# Sheet1.net
KiCad netlist of a schematic drawn in Altium Designer
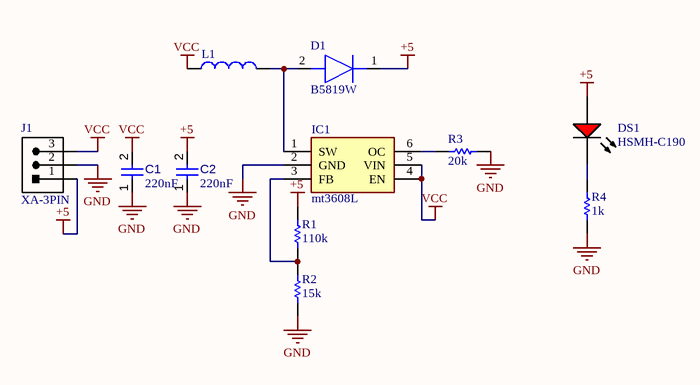
[diagram p0: Sheet1.SchDoc]

(export (version "E")
  (design (tool "Eeschema 10.0.6"))
  (components
    (comp (ref "C1")
      (value "220nF")
      (footprint "CAPC0805(2012)145_L")
      (fields (field (name "Comment") "C0805C224K5RACTU"))
      (libsource (lib "Americas- Northwestern Formula Racing- Northwestern University") (part "CAP-NP-2"))
    )
    (comp (ref "C2")
      (value "220nF")
      (footprint "CAPC0805(2012)145_L")
      (fields (field (name "Comment") "C0805C224K5RACTU"))
      (libsource (lib "Americas- Northwestern Formula Racing- Northwestern University") (part "CAP-NP-2"))
    )
    (comp (ref "D1")
      (value "B5819W")
      (footprint "SamacSys:SOD3716X125N")
      (description "Diode")
      (libsource (lib "*") (part "B5819W"))
    )
    (comp (ref "DS1")
      (value "HSMH-C190")
      (footprint "AVAG-HSMX-C190_V")
      (description "LED Uni-Color Red, 65 mW, 20 mA, -40 to 85 degC, 2-Pin SMD, RoHS, Tape and Reel")
      (fields (field (name "POWER") "78mW") (field (name "MANUFACTURER") "Avago"))
      (libsource (lib "Americas- Northwestern Formula Racing- Northwestern University") (part "LED-RED-AK-2"))
    )
    (comp (ref "IC1")
      (value "mt3608L")
      (footprint "SamacSys:SOT95P280X145-6N")
      (description "Integrated Circuit")
      (libsource (lib "*") (part "mt3608L"))
    )
    (comp (ref "J1")
      (value "XA-3PIN")
      (footprint "XA-3PIN-Footprint-1")
      (description "3 pin JST Connector")
      (libsource (lib "Americas- Northwestern Formula Racing- Northwestern University") (part "XA-3PIN"))
    )
    (comp (ref "L1")
      (value "MBKK2012T4R7M")
      (footprint "INDC2520X120X60LL20T20")
      (description "General Purpose Inductor, 4.7uH, 20%, 1 Element, Metal-Core, SMD, 0805")
      (fields (field (name "TOLERANCE") "20%"))
      (libsource (lib "Americas- Northwestern Formula Racing- Northwestern University") (part "IND-2"))
    )
    (comp (ref "R1")
      (value "110k")
      (footprint "RESC0402(1005)_L")
      (fields
        (field (name "POWER") "50mW")
        (field (name "TOLERANCE") "1%")
        (field (name "Comment") "ERJ-1GNF1103C")
      )
      (libsource (lib "Americas- Northwestern Formula Racing- Northwestern University") (part "RES-2"))
    )
    (comp (ref "R2")
      (value "15k")
      (footprint "RESC0603(1608)_L")
      (description "Fixed Resistor, Thin Film, 0.1W, 15000ohm, 75V, 0.1% +/-Tol, 25ppm/Cel, Surface Mount, 0603")
      (fields (field (name "TOLERANCE") "0.1%") (field (name "POWER") "100mW"))
      (libsource (lib "Americas- Northwestern Formula Racing- Northwestern University") (part "RES-2"))
    )
    (comp (ref "R3")
      (value "20k")
      (footprint "RESC1608X55X30LL15T15")
      (fields
        (field (name "TOLERANCE") "1%")
        (field (name "POWER") "100mW")
        (field (name "Comment") "ERJ-3EKF2002V")
      )
      (libsource (lib "Americas- Northwestern Formula Racing- Northwestern University") (part "RES-2"))
    )
    (comp (ref "R4")
      (value "1k")
      (footprint "RESC0603(1608)_L")
      (fields
        (field (name "TOLERANCE") "1%")
        (field (name "POWER") "100mW")
        (field (name "Comment") "RMCF0603FT1K00")
      )
      (libsource (lib "Americas- Northwestern Formula Racing- Northwestern University") (part "RES-2"))
    )
  )
  (nets
    (net (code "1") (name "+5") (class "Default")
      (node (ref "C2") (pin "2") (pinfunction "2_2") (pintype "passive"))
      (node (ref "D1") (pin "1") (pinfunction "K_1") (pintype "passive"))
      (node (ref "DS1") (pin "1") (pinfunction "A_1") (pintype "passive"))
      (node (ref "J1") (pin "1") (pinfunction "1_1") (pintype "passive"))
      (node (ref "R1") (pin "2") (pinfunction "2_2") (pintype "passive"))
    )
    (net (code "2") (name "GND") (class "Default")
      (node (ref "C1") (pin "1") (pinfunction "1_1") (pintype "passive"))
      (node (ref "C2") (pin "1") (pinfunction "1_1") (pintype "passive"))
      (node (ref "IC1") (pin "2") (pinfunction "GND_2") (pintype "passive"))
      (node (ref "J1") (pin "2") (pinfunction "2_2") (pintype "passive"))
      (node (ref "R2") (pin "2") (pinfunction "2_2") (pintype "passive"))
      (node (ref "R3") (pin "2") (pinfunction "2_2") (pintype "passive"))
      (node (ref "R4") (pin "2") (pinfunction "2_2") (pintype "passive"))
    )
    (net (code "3") (name "Net-(D1-A)") (class "Default")
      (node (ref "D1") (pin "2") (pinfunction "A_2") (pintype "passive"))
      (node (ref "IC1") (pin "1") (pinfunction "SW_1") (pintype "passive"))
      (node (ref "L1") (pin "2") (pinfunction "2_2") (pintype "passive"))
    )
    (net (code "4") (name "Net-(DS1-K)") (class "Default")
      (node (ref "DS1") (pin "2") (pinfunction "K_2") (pintype "passive"))
      (node (ref "R4") (pin "1") (pinfunction "1_1") (pintype "passive"))
    )
    (net (code "5") (name "Net-(IC1-FB)") (class "Default")
      (node (ref "IC1") (pin "3") (pinfunction "FB_3") (pintype "passive"))
      (node (ref "R1") (pin "1") (pinfunction "1_1") (pintype "passive"))
      (node (ref "R2") (pin "1") (pinfunction "1_1") (pintype "passive"))
    )
    (net (code "6") (name "Net-(IC1-OC)") (class "Default")
      (node (ref "IC1") (pin "6") (pinfunction "OC_6") (pintype "passive"))
      (node (ref "R3") (pin "1") (pinfunction "1_1") (pintype "passive"))
    )
    (net (code "7") (name "VCC") (class "Default")
      (node (ref "C1") (pin "2") (pinfunction "2_2") (pintype "passive"))
      (node (ref "IC1") (pin "4") (pinfunction "EN_4") (pintype "passive"))
      (node (ref "IC1") (pin "5") (pinfunction "VIN_5") (pintype "passive"))
      (node (ref "J1") (pin "3") (pinfunction "3_3") (pintype "passive"))
      (node (ref "L1") (pin "1") (pinfunction "1_1") (pintype "passive"))
    )
  )
)
